# Ethernet.net
KiCad netlist of a schematic drawn in Altium Designer
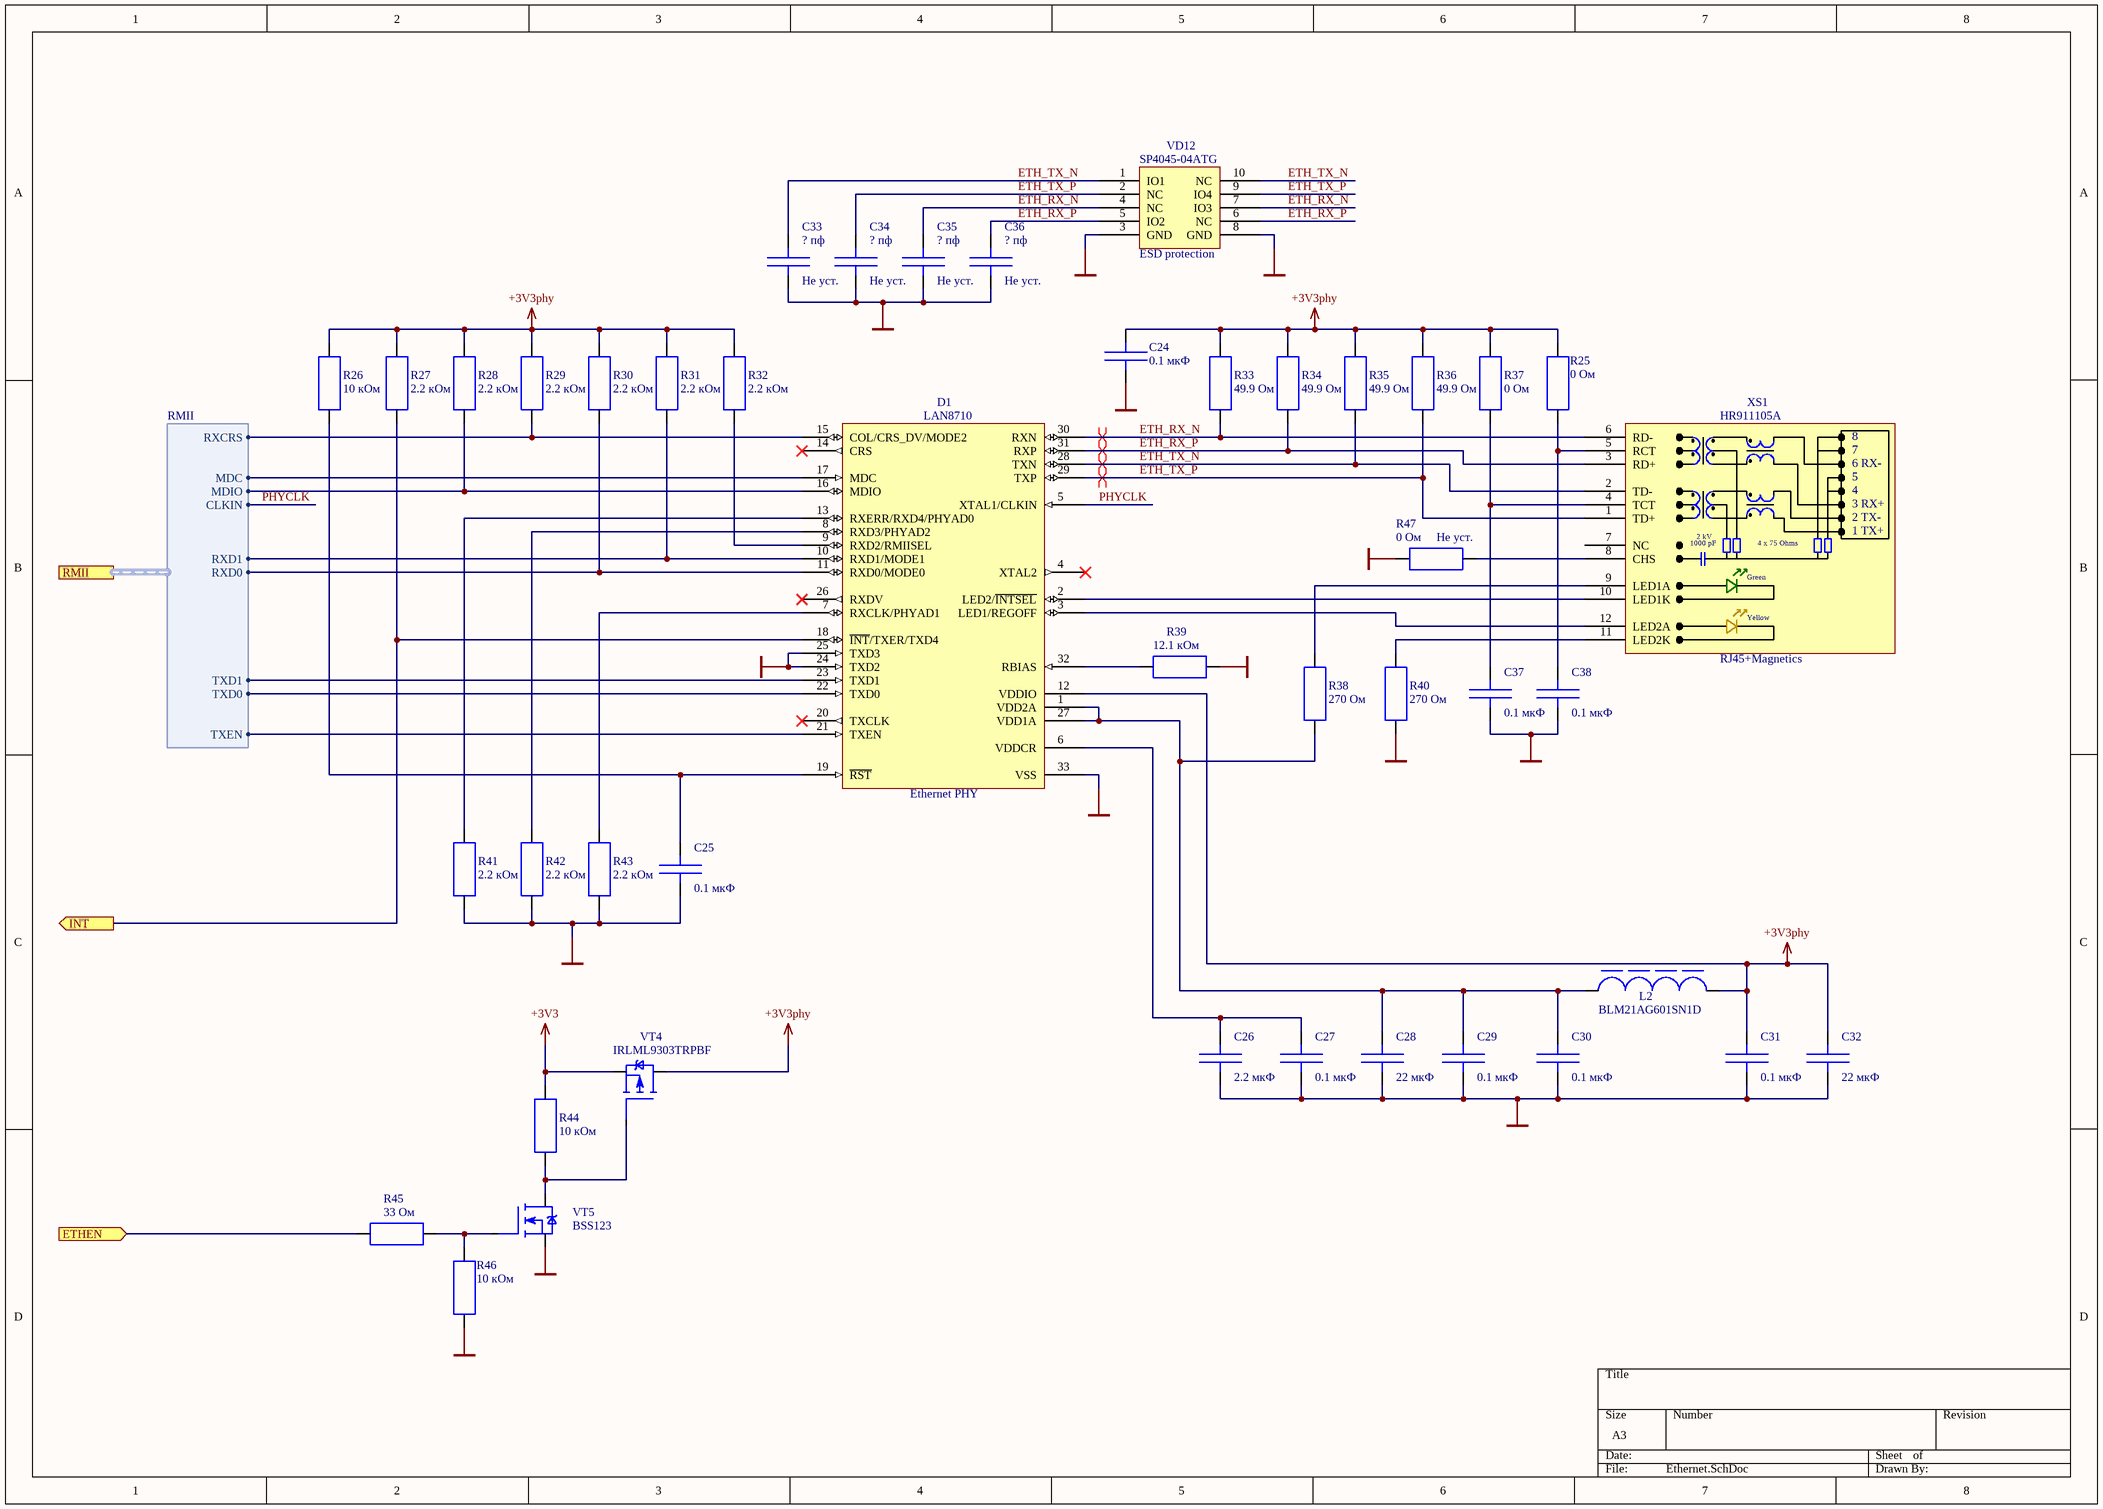
[diagram p0: Ethernet.SchDoc]

(export (version "E")
  (design (tool "Eeschema 10.0.6"))
  (components
    (comp (ref "C24")
      (value "0.1 мкФ")
      (footprint "CAP_0603-1608")
      (description "Конденсатор")
      (fields (field (name "VOLTAGE") "50 В") (field (name "Comment") "Cap"))
      (libsource (lib "GOST_Generic") (part "Cap"))
    )
    (comp (ref "C25")
      (value "0.1 мкФ")
      (footprint "CAP_0603-1608")
      (description "Конденсатор")
      (fields (field (name "VOLTAGE") "50 В") (field (name "Comment") "Cap"))
      (libsource (lib "GOST_Generic") (part "Cap"))
    )
    (comp (ref "C26")
      (value "2.2 мкФ")
      (footprint "CAP_0603-1608")
      (description "Конденсатор")
      (fields (field (name "VOLTAGE") "10 В") (field (name "Comment") "Cap"))
      (libsource (lib "GOST_Generic") (part "Cap"))
    )
    (comp (ref "C27")
      (value "0.1 мкФ")
      (footprint "CAP_0603-1608")
      (description "Конденсатор")
      (fields (field (name "VOLTAGE") "50 В") (field (name "Comment") "Cap"))
      (libsource (lib "GOST_Generic") (part "Cap"))
    )
    (comp (ref "C28")
      (value "22 мкФ")
      (footprint "CAP_0805-2012")
      (description "Конденсатор")
      (fields (field (name "VOLTAGE") "6.3 В") (field (name "Comment") "Cap"))
      (libsource (lib "GOST_Generic") (part "Cap"))
    )
    (comp (ref "C29")
      (value "0.1 мкФ")
      (footprint "CAP_0603-1608")
      (description "Конденсатор")
      (fields (field (name "VOLTAGE") "50 В") (field (name "Comment") "Cap"))
      (libsource (lib "GOST_Generic") (part "Cap"))
    )
    (comp (ref "C30")
      (value "0.1 мкФ")
      (footprint "CAP_0603-1608")
      (description "Конденсатор")
      (fields (field (name "VOLTAGE") "50 В") (field (name "Comment") "Cap"))
      (libsource (lib "GOST_Generic") (part "Cap"))
    )
    (comp (ref "C31")
      (value "0.1 мкФ")
      (footprint "CAP_0603-1608")
      (description "Конденсатор")
      (fields (field (name "VOLTAGE") "50 В") (field (name "Comment") "Cap"))
      (libsource (lib "GOST_Generic") (part "Cap"))
    )
    (comp (ref "C32")
      (value "22 мкФ")
      (footprint "CAP_0805-2012")
      (description "Конденсатор")
      (fields (field (name "VOLTAGE") "6.3 В") (field (name "Comment") "Cap"))
      (libsource (lib "GOST_Generic") (part "Cap"))
    )
    (comp (ref "C33")
      (value "Не уст.")
      (footprint "CAP_0603-1608")
      (description "Конденсатор")
      (fields (field (name "VOLTAGE") "50 В") (field (name "ALTIUM_VALUE") "? пф"))
      (libsource (lib "GOST_Generic") (part "Cap"))
    )
    (comp (ref "C34")
      (value "Не уст.")
      (footprint "CAP_0603-1608")
      (description "Конденсатор")
      (fields (field (name "VOLTAGE") "50 В") (field (name "ALTIUM_VALUE") "? пф"))
      (libsource (lib "GOST_Generic") (part "Cap"))
    )
    (comp (ref "C35")
      (value "Не уст.")
      (footprint "CAP_0603-1608")
      (description "Конденсатор")
      (fields (field (name "VOLTAGE") "50 В") (field (name "ALTIUM_VALUE") "? пф"))
      (libsource (lib "GOST_Generic") (part "Cap"))
    )
    (comp (ref "C36")
      (value "Не уст.")
      (footprint "CAP_0603-1608")
      (description "Конденсатор")
      (fields (field (name "VOLTAGE") "50 В") (field (name "ALTIUM_VALUE") "? пф"))
      (libsource (lib "GOST_Generic") (part "Cap"))
    )
    (comp (ref "C37")
      (value "0.1 мкФ")
      (footprint "CAP_0603-1608")
      (description "Конденсатор")
      (fields (field (name "VOLTAGE") "50 В") (field (name "Comment") "Cap"))
      (libsource (lib "GOST_Generic") (part "Cap"))
    )
    (comp (ref "C38")
      (value "0.1 мкФ")
      (footprint "CAP_0603-1608")
      (description "Конденсатор")
      (fields (field (name "VOLTAGE") "50 В") (field (name "Comment") "Cap"))
      (libsource (lib "GOST_Generic") (part "Cap"))
    )
    (comp (ref "D1")
      (value "Ethernet PHY")
      (footprint "QFN-0.5-32")
      (description "10/100 Ethernet MII/RMII Transceiver")
      (fields (field (name "TYPE") "LAN8710"))
      (libsource (lib "Микросхемы интерфейсов") (part "LAN8710"))
    )
    (comp (ref "L2")
      (value "Inductor_Ferrite")
      (footprint "CAP_0805-2012")
      (description "Катушка идуктивности с магнитодиэлектрическим магнитопроводом")
      (fields (field (name "TYPE") "BLM21AG601SN1D"))
      (libsource (lib "GOST_Generic") (part "Inductor_Ferrite"))
    )
    (comp (ref "R25")
      (value "0 Ом")
      (footprint "RES_0603-1608")
      (description "Резистор постоянный")
      (fields (field (name "POWER") "0.125 W") (field (name "TOLERANCE") "5%"))
      (libsource (lib "GOST_Generic") (part "Res"))
    )
    (comp (ref "R26")
      (value "10 кОм")
      (footprint "RES_0603-1608")
      (description "Резистор постоянный")
      (fields (field (name "POWER") "0.125 W") (field (name "TOLERANCE") "5%"))
      (libsource (lib "GOST_Generic") (part "Res"))
    )
    (comp (ref "R27")
      (value "2.2 кОм")
      (footprint "RES_0603-1608")
      (description "Резистор постоянный")
      (fields (field (name "POWER") "0.125 W") (field (name "TOLERANCE") "5%"))
      (libsource (lib "GOST_Generic") (part "Res"))
    )
    (comp (ref "R28")
      (value "2.2 кОм")
      (footprint "RES_0603-1608")
      (description "Резистор постоянный")
      (fields (field (name "POWER") "0.125 W") (field (name "TOLERANCE") "5%"))
      (libsource (lib "GOST_Generic") (part "Res"))
    )
    (comp (ref "R29")
      (value "2.2 кОм")
      (footprint "RES_0603-1608")
      (description "Резистор постоянный")
      (fields (field (name "POWER") "0.125 W") (field (name "TOLERANCE") "5%"))
      (libsource (lib "GOST_Generic") (part "Res"))
    )
    (comp (ref "R30")
      (value "2.2 кОм")
      (footprint "RES_0603-1608")
      (description "Резистор постоянный")
      (fields (field (name "POWER") "0.125 W") (field (name "TOLERANCE") "5%"))
      (libsource (lib "GOST_Generic") (part "Res"))
    )
    (comp (ref "R31")
      (value "2.2 кОм")
      (footprint "RES_0603-1608")
      (description "Резистор постоянный")
      (fields (field (name "POWER") "0.125 W") (field (name "TOLERANCE") "5%"))
      (libsource (lib "GOST_Generic") (part "Res"))
    )
    (comp (ref "R32")
      (value "2.2 кОм")
      (footprint "RES_0603-1608")
      (description "Резистор постоянный")
      (fields (field (name "POWER") "0.125 W") (field (name "TOLERANCE") "5%"))
      (libsource (lib "GOST_Generic") (part "Res"))
    )
    (comp (ref "R33")
      (value "49.9 Ом")
      (footprint "RES_0603-1608")
      (description "Резистор постоянный")
      (fields (field (name "POWER") "0.125 W") (field (name "TOLERANCE") "5%"))
      (libsource (lib "GOST_Generic") (part "Res"))
    )
    (comp (ref "R34")
      (value "49.9 Ом")
      (footprint "RES_0603-1608")
      (description "Резистор постоянный")
      (fields (field (name "POWER") "0.125 W") (field (name "TOLERANCE") "5%"))
      (libsource (lib "GOST_Generic") (part "Res"))
    )
    (comp (ref "R35")
      (value "49.9 Ом")
      (footprint "RES_0603-1608")
      (description "Резистор постоянный")
      (fields (field (name "POWER") "0.125 W") (field (name "TOLERANCE") "5%"))
      (libsource (lib "GOST_Generic") (part "Res"))
    )
    (comp (ref "R36")
      (value "49.9 Ом")
      (footprint "RES_0603-1608")
      (description "Резистор постоянный")
      (fields (field (name "POWER") "0.125 W") (field (name "TOLERANCE") "5%"))
      (libsource (lib "GOST_Generic") (part "Res"))
    )
    (comp (ref "R37")
      (value "0 Ом")
      (footprint "RES_0603-1608")
      (description "Резистор постоянный")
      (fields (field (name "POWER") "0.125 W") (field (name "TOLERANCE") "5%"))
      (libsource (lib "GOST_Generic") (part "Res"))
    )
    (comp (ref "R38")
      (value "270 Ом")
      (footprint "RES_0603-1608")
      (description "Резистор постоянный")
      (fields (field (name "POWER") "0.125 W") (field (name "TOLERANCE") "5%"))
      (libsource (lib "GOST_Generic") (part "Res"))
    )
    (comp (ref "R39")
      (value "12.1 кОм")
      (footprint "RES_0603-1608")
      (description "Резистор постоянный")
      (fields (field (name "POWER") "0.125 W") (field (name "TOLERANCE") "5%"))
      (libsource (lib "GOST_Generic") (part "Res"))
    )
    (comp (ref "R40")
      (value "270 Ом")
      (footprint "RES_0603-1608")
      (description "Резистор постоянный")
      (fields (field (name "POWER") "0.125 W") (field (name "TOLERANCE") "5%"))
      (libsource (lib "GOST_Generic") (part "Res"))
    )
    (comp (ref "R41")
      (value "2.2 кОм")
      (footprint "RES_0603-1608")
      (description "Резистор постоянный")
      (fields (field (name "POWER") "0.125 W") (field (name "TOLERANCE") "5%"))
      (libsource (lib "GOST_Generic") (part "Res"))
    )
    (comp (ref "R42")
      (value "2.2 кОм")
      (footprint "RES_0603-1608")
      (description "Резистор постоянный")
      (fields (field (name "POWER") "0.125 W") (field (name "TOLERANCE") "5%"))
      (libsource (lib "GOST_Generic") (part "Res"))
    )
    (comp (ref "R43")
      (value "2.2 кОм")
      (footprint "RES_0603-1608")
      (description "Резистор постоянный")
      (fields (field (name "POWER") "0.125 W") (field (name "TOLERANCE") "5%"))
      (libsource (lib "GOST_Generic") (part "Res"))
    )
    (comp (ref "R44")
      (value "10 кОм")
      (footprint "RES_0603-1608")
      (description "ЧИП резистор постоянный")
      (fields (field (name "POWER") "0.1 W") (field (name "TOLERANCE") "5%"))
      (libsource (lib "GOST_Generic") (part "Res"))
    )
    (comp (ref "R45")
      (value "33 Ом")
      (footprint "RES_0603-1608")
      (description "ЧИП резистор постоянный")
      (fields (field (name "POWER") "0.1 W") (field (name "TOLERANCE") "5%"))
      (libsource (lib "GOST_Generic") (part "Res"))
    )
    (comp (ref "R46")
      (value "10 кОм")
      (footprint "RES_0603-1608")
      (description "ЧИП резистор постоянный")
      (fields (field (name "POWER") "0.1 W") (field (name "TOLERANCE") "5%"))
      (libsource (lib "GOST_Generic") (part "Res"))
    )
    (comp (ref "R47")
      (value "Не уст.")
      (footprint "RES_0603-1608")
      (description "Резистор постоянный")
      (fields
        (field (name "POWER") "0.125 W")
        (field (name "TOLERANCE") "5%")
        (field (name "ALTIUM_VALUE") "0 Ом")
      )
      (libsource (lib "GOST_Generic") (part "Res"))
    )
    (comp (ref "VD12")
      (value "ESD protection")
      (footprint "MSOP-0.5-10")
      (description "1.5pF 24A Diode Array")
      (fields (field (name "TYPE") "SP4045-04ATG"))
      (libsource (lib "Устройства защиты от ESD") (part "SP4045-04ATG"))
    )
    (comp (ref "VT4")
      (value "Transistor_P-MOSFET_Enh_Bulk_Shot")
      (footprint "SOT-23-3")
      (fields (field (name "TYPE") "IRLML9303TRPBF"))
      (libsource (lib "GOST_Generic") (part "Transistor_P-MOSFET_Enh_Bulk_Shot"))
    )
    (comp (ref "VT5")
      (value "Transistor_N-MOSFET_Enh_Bulk_Shot")
      (footprint "SOT-23-3")
      (fields (field (name "TYPE") "BSS123"))
      (libsource (lib "GOST_Generic") (part "Transistor_N-MOSFET_Enh_Bulk_Shot"))
    )
    (comp (ref "XS1")
      (value "RJ45+Magnetics")
      (footprint "HR911105A")
      (description "RJ-45 socket with magnetics")
      (fields (field (name "TYPE") "HR911105A"))
      (libsource (lib "Стандартные соединители") (part "HR911105A"))
    )
  )
  (nets
    (net (code "2") (name "+3V3") (class "Default")
      (node (ref "R44") (pin "1") (pintype "passive"))
      (node (ref "VT4") (pin "2") (pinfunction "S_2") (pintype "passive"))
    )
    (net (code "3") (name "+3V3phy") (class "Default")
      (node (ref "C24") (pin "1") (pinfunction "1_1") (pintype "passive"))
      (node (ref "C31") (pin "2") (pinfunction "2_2") (pintype "passive"))
      (node (ref "C32") (pin "2") (pinfunction "2_2") (pintype "passive"))
      (node (ref "D1") (pin "12") (pinfunction "VDDIO_12") (pintype "power_in"))
      (node (ref "L2") (pin "2") (pinfunction "2_2") (pintype "passive"))
      (node (ref "R25") (pin "1") (pintype "passive"))
      (node (ref "R26") (pin "2") (pintype "passive"))
      (node (ref "R27") (pin "2") (pintype "passive"))
      (node (ref "R28") (pin "2") (pintype "passive"))
      (node (ref "R29") (pin "2") (pintype "passive"))
      (node (ref "R30") (pin "2") (pintype "passive"))
      (node (ref "R31") (pin "2") (pintype "passive"))
      (node (ref "R32") (pin "2") (pintype "passive"))
      (node (ref "R33") (pin "2") (pintype "passive"))
      (node (ref "R34") (pin "2") (pintype "passive"))
      (node (ref "R35") (pin "2") (pintype "passive"))
      (node (ref "R36") (pin "2") (pintype "passive"))
      (node (ref "R37") (pin "2") (pintype "passive"))
      (node (ref "VT4") (pin "3") (pinfunction "D_3") (pintype "passive"))
    )
    (net (code "4") (name "/ETHEN") (class "Default") (node (ref "R45") (pin "2") (pintype "passive")))
    (net (code "5") (name "/ETH_RX_N") (class "Default")
      (node (ref "C35") (pin "1") (pinfunction "1_1") (pintype "passive"))
      (node (ref "D1") (pin "30") (pinfunction "RXN_30") (pintype "bidirectional"))
      (node (ref "R33") (pin "1") (pintype "passive"))
      (node (ref "VD12") (pin "4") (pinfunction "NC_4") (pintype "passive"))
      (node (ref "VD12") (pin "7") (pinfunction "IO3_7") (pintype "passive"))
      (node (ref "XS1") (pin "6") (pinfunction "RD-_6") (pintype "passive"))
    )
    (net (code "6") (name "/ETH_RX_P") (class "Default")
      (node (ref "C36") (pin "1") (pinfunction "1_1") (pintype "passive"))
      (node (ref "D1") (pin "31") (pinfunction "RXP_31") (pintype "bidirectional"))
      (node (ref "R34") (pin "1") (pintype "passive"))
      (node (ref "VD12") (pin "5") (pinfunction "IO2_5") (pintype "passive"))
      (node (ref "VD12") (pin "6") (pinfunction "NC_6") (pintype "passive"))
      (node (ref "XS1") (pin "3") (pinfunction "RD+_3") (pintype "passive"))
    )
    (net (code "7") (name "/ETH_TX_N") (class "Default")
      (node (ref "C33") (pin "1") (pinfunction "1_1") (pintype "passive"))
      (node (ref "D1") (pin "28") (pinfunction "TXN_28") (pintype "bidirectional"))
      (node (ref "R35") (pin "1") (pintype "passive"))
      (node (ref "VD12") (pin "1") (pinfunction "IO1_1") (pintype "passive"))
      (node (ref "VD12") (pin "10") (pinfunction "NC_10") (pintype "passive"))
      (node (ref "XS1") (pin "2") (pinfunction "TD-_2") (pintype "passive"))
    )
    (net (code "8") (name "/ETH_TX_P") (class "Default")
      (node (ref "C34") (pin "1") (pinfunction "1_1") (pintype "passive"))
      (node (ref "D1") (pin "29") (pinfunction "TXP_29") (pintype "bidirectional"))
      (node (ref "R36") (pin "1") (pintype "passive"))
      (node (ref "VD12") (pin "2") (pinfunction "NC_2") (pintype "passive"))
      (node (ref "VD12") (pin "9") (pinfunction "IO4_9") (pintype "passive"))
      (node (ref "XS1") (pin "1") (pinfunction "TD+_1") (pintype "passive"))
    )
    (net (code "9") (name "/INT") (class "Default")
      (node (ref "D1") (pin "18") (pinfunction "~{INT}/TXER/TXD4_18") (pintype "bidirectional"))
      (node (ref "R27") (pin "1") (pintype "passive"))
    )
    (net (code "10") (name "/MDC") (class "Default")
      (node (ref "D1") (pin "17") (pinfunction "MDC_17") (pintype "input"))
    )
    (net (code "11") (name "/MDIO") (class "Default")
      (node (ref "D1") (pin "16") (pinfunction "MDIO_16") (pintype "bidirectional"))
      (node (ref "R28") (pin "1") (pintype "passive"))
    )
    (net (code "12") (name "/PHYCLK") (class "Default")
      (node (ref "D1") (pin "5") (pinfunction "XTAL1/CLKIN_5") (pintype "input"))
    )
    (net (code "13") (name "/RXCRS") (class "Default")
      (node (ref "D1") (pin "15") (pinfunction "COL/CRS_DV/MODE2_15") (pintype "bidirectional"))
      (node (ref "R29") (pin "1") (pintype "passive"))
    )
    (net (code "14") (name "/RXD0") (class "Default")
      (node (ref "D1") (pin "11") (pinfunction "RXD0/MODE0_11") (pintype "bidirectional"))
      (node (ref "R30") (pin "1") (pintype "passive"))
    )
    (net (code "15") (name "/RXD1") (class "Default")
      (node (ref "D1") (pin "10") (pinfunction "RXD1/MODE1_10") (pintype "bidirectional"))
      (node (ref "R31") (pin "1") (pintype "passive"))
    )
    (net (code "16") (name "/TXD0") (class "Default")
      (node (ref "D1") (pin "22") (pinfunction "TXD0_22") (pintype "input"))
    )
    (net (code "17") (name "/TXD1") (class "Default")
      (node (ref "D1") (pin "23") (pinfunction "TXD1_23") (pintype "input"))
    )
    (net (code "18") (name "/TXEN") (class "Default")
      (node (ref "D1") (pin "21") (pinfunction "TXEN_21") (pintype "input"))
    )
    (net (code "20") (name "GND") (class "Default")
      (node (ref "C24") (pin "2") (pinfunction "2_2") (pintype "passive"))
      (node (ref "C25") (pin "1") (pinfunction "1_1") (pintype "passive"))
      (node (ref "C26") (pin "1") (pinfunction "1_1") (pintype "passive"))
      (node (ref "C27") (pin "1") (pinfunction "1_1") (pintype "passive"))
      (node (ref "C28") (pin "1") (pinfunction "1_1") (pintype "passive"))
      (node (ref "C29") (pin "1") (pinfunction "1_1") (pintype "passive"))
      (node (ref "C30") (pin "1") (pinfunction "1_1") (pintype "passive"))
      (node (ref "C31") (pin "1") (pinfunction "1_1") (pintype "passive"))
      (node (ref "C32") (pin "1") (pinfunction "1_1") (pintype "passive"))
      (node (ref "C33") (pin "2") (pinfunction "2_2") (pintype "passive"))
      (node (ref "C34") (pin "2") (pinfunction "2_2") (pintype "passive"))
      (node (ref "C35") (pin "2") (pinfunction "2_2") (pintype "passive"))
      (node (ref "C36") (pin "2") (pinfunction "2_2") (pintype "passive"))
      (node (ref "C37") (pin "2") (pinfunction "2_2") (pintype "passive"))
      (node (ref "C38") (pin "2") (pinfunction "2_2") (pintype "passive"))
      (node (ref "D1") (pin "24") (pinfunction "TXD2_24") (pintype "input"))
      (node (ref "D1") (pin "25") (pinfunction "TXD3_25") (pintype "input"))
      (node (ref "D1") (pin "33") (pinfunction "VSS_33") (pintype "power_in"))
      (node (ref "R39") (pin "2") (pintype "passive"))
      (node (ref "R40") (pin "1") (pintype "passive"))
      (node (ref "R41") (pin "2") (pintype "passive"))
      (node (ref "R42") (pin "2") (pintype "passive"))
      (node (ref "R43") (pin "2") (pintype "passive"))
      (node (ref "R46") (pin "2") (pintype "passive"))
      (node (ref "R47") (pin "1") (pintype "passive"))
      (node (ref "VD12") (pin "3") (pinfunction "GND_3") (pintype "power_in"))
      (node (ref "VD12") (pin "8") (pinfunction "GND_8") (pintype "power_in"))
      (node (ref "VT5") (pin "2") (pinfunction "S_2") (pintype "passive"))
    )
    (net (code "21") (name "Net-(D1-LED1{slash}REGOFF)") (class "Default")
      (node (ref "D1") (pin "3") (pinfunction "LED1/REGOFF_3") (pintype "bidirectional"))
      (node (ref "XS1") (pin "12") (pinfunction "LED2A_12") (pintype "passive"))
    )
    (net (code "22") (name "Net-(D1-LED2{slash}~{INTSEL})") (class "Default")
      (node (ref "D1") (pin "2") (pinfunction "LED2/~{INTSEL}_2") (pintype "bidirectional"))
      (node (ref "XS1") (pin "10") (pinfunction "LED1K_10") (pintype "passive"))
    )
    (net (code "23") (name "Net-(D1-RBIAS)") (class "Default")
      (node (ref "D1") (pin "32") (pinfunction "RBIAS_32") (pintype "input"))
      (node (ref "R39") (pin "1") (pintype "passive"))
    )
    (net (code "24") (name "Net-(D1-RXCLK{slash}PHYAD1)") (class "Default")
      (node (ref "D1") (pin "7") (pinfunction "RXCLK/PHYAD1_7") (pintype "bidirectional"))
      (node (ref "R43") (pin "1") (pintype "passive"))
    )
    (net (code "25") (name "Net-(D1-RXD2{slash}RMIISEL)") (class "Default")
      (node (ref "D1") (pin "9") (pinfunction "RXD2/RMIISEL_9") (pintype "bidirectional"))
      (node (ref "R32") (pin "1") (pintype "passive"))
    )
    (net (code "26") (name "Net-(D1-RXD3{slash}PHYAD2)") (class "Default")
      (node (ref "D1") (pin "8") (pinfunction "RXD3/PHYAD2_8") (pintype "bidirectional"))
      (node (ref "R42") (pin "1") (pintype "passive"))
    )
    (net (code "27") (name "Net-(D1-RXERR{slash}RXD4{slash}PHYAD0)") (class "Default")
      (node (ref "D1") (pin "13") (pinfunction "RXERR/RXD4/PHYAD0_13") (pintype "bidirectional"))
      (node (ref "R41") (pin "1") (pintype "passive"))
    )
    (net (code "28") (name "Net-(D1-VDD1A)") (class "Default")
      (node (ref "C28") (pin "2") (pinfunction "2_2") (pintype "passive"))
      (node (ref "C29") (pin "2") (pinfunction "2_2") (pintype "passive"))
      (node (ref "C30") (pin "2") (pinfunction "2_2") (pintype "passive"))
      (node (ref "D1") (pin "1") (pinfunction "VDD2A_1") (pintype "power_in"))
      (node (ref "D1") (pin "27") (pinfunction "VDD1A_27") (pintype "power_in"))
      (node (ref "L2") (pin "1") (pinfunction "1_1") (pintype "passive"))
      (node (ref "R38") (pin "2") (pintype "passive"))
    )
    (net (code "29") (name "Net-(D1-VDDCR)") (class "Default")
      (node (ref "C26") (pin "2") (pinfunction "2_2") (pintype "passive"))
      (node (ref "C27") (pin "2") (pinfunction "2_2") (pintype "passive"))
      (node (ref "D1") (pin "6") (pinfunction "VDDCR_6") (pintype "power_in"))
    )
    (net (code "30") (name "Net-(D1-~{RST})") (class "Default")
      (node (ref "C25") (pin "2") (pinfunction "2_2") (pintype "passive"))
      (node (ref "D1") (pin "19") (pinfunction "~{RST}_19") (pintype "input"))
      (node (ref "R26") (pin "1") (pintype "passive"))
    )
    (net (code "31") (name "Net-(VT4-G)") (class "Default")
      (node (ref "R44") (pin "2") (pintype "passive"))
      (node (ref "VT4") (pin "1") (pinfunction "G_1") (pintype "passive"))
      (node (ref "VT5") (pin "3") (pinfunction "D_3") (pintype "passive"))
    )
    (net (code "32") (name "Net-(VT5-G)") (class "Default")
      (node (ref "R45") (pin "1") (pintype "passive"))
      (node (ref "R46") (pin "1") (pintype "passive"))
      (node (ref "VT5") (pin "1") (pinfunction "G_1") (pintype "passive"))
    )
    (net (code "33") (name "Net-(XS1-CHS)") (class "Default")
      (node (ref "R47") (pin "2") (pintype "passive"))
      (node (ref "XS1") (pin "8") (pinfunction "CHS_8") (pintype "passive"))
    )
    (net (code "34") (name "Net-(XS1-LED1A)") (class "Default")
      (node (ref "R38") (pin "1") (pintype "passive"))
      (node (ref "XS1") (pin "9") (pinfunction "LED1A_9") (pintype "passive"))
    )
    (net (code "35") (name "Net-(XS1-LED2K)") (class "Default")
      (node (ref "R40") (pin "2") (pintype "passive"))
      (node (ref "XS1") (pin "11") (pinfunction "LED2K_11") (pintype "passive"))
    )
    (net (code "36") (name "Net-(XS1-RCT)") (class "Default")
      (node (ref "C38") (pin "1") (pinfunction "1_1") (pintype "passive"))
      (node (ref "R25") (pin "2") (pintype "passive"))
      (node (ref "XS1") (pin "5") (pinfunction "RCT_5") (pintype "passive"))
    )
    (net (code "37") (name "Net-(XS1-TCT)") (class "Default")
      (node (ref "C37") (pin "1") (pinfunction "1_1") (pintype "passive"))
      (node (ref "R37") (pin "1") (pintype "passive"))
      (node (ref "XS1") (pin "4") (pinfunction "TCT_4") (pintype "passive"))
    )
    (net (code "38") (name "unconnected-(D1-CRS-Pad14)") (class "Default")
      (node (ref "D1") (pin "14") (pinfunction "CRS_14") (pintype "output+no_connect"))
    )
    (net (code "39") (name "unconnected-(D1-RXDV-Pad26)") (class "Default")
      (node (ref "D1") (pin "26") (pinfunction "RXDV_26") (pintype "output+no_connect"))
    )
    (net (code "40") (name "unconnected-(D1-TXCLK-Pad20)") (class "Default")
      (node (ref "D1") (pin "20") (pinfunction "TXCLK_20") (pintype "output+no_connect"))
    )
    (net (code "41") (name "unconnected-(D1-XTAL2-Pad4)") (class "Default")
      (node (ref "D1") (pin "4") (pinfunction "XTAL2_4") (pintype "output+no_connect"))
    )
    (net (code "42") (name "unconnected-(XS1-NC-Pad7)") (class "Default")
      (node (ref "XS1") (pin "7") (pinfunction "NC_7") (pintype "passive"))
    )
  )
)
